# Qwiic_keypad.net
KiCad netlist of a schematic drawn in EAGLE
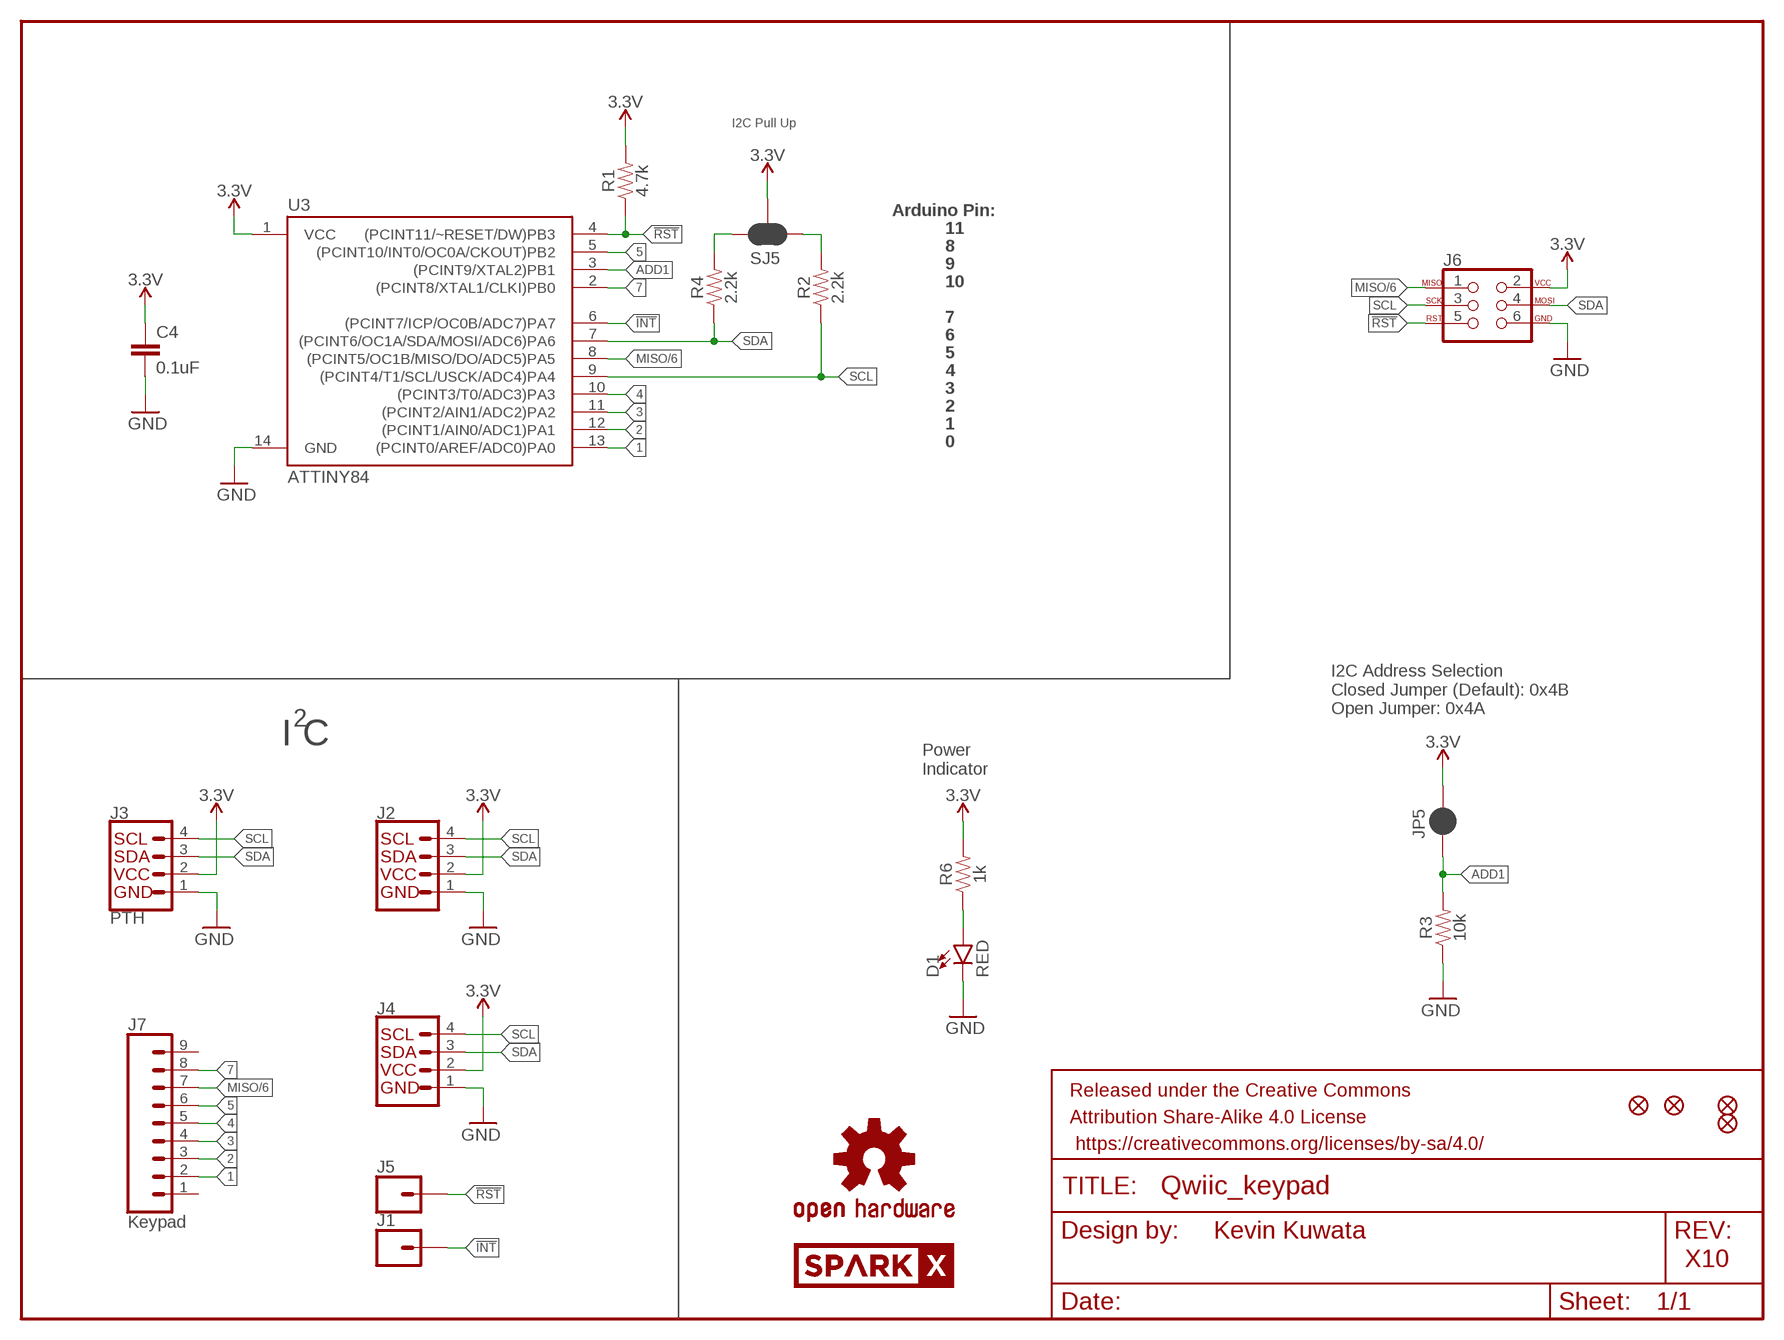
[diagram p0: schematic, sheet 1]

(export (version "E")
  (design (tool "Eeschema 10.0.6"))
  (components
    (comp (ref "C4")
      (value "0.1uF")
      (footprint "eagle-import:0603")
      (libsource (lib "eagle-import") (part "0.1UF-0603-25V-(+80/-20%)"))
    )
    (comp (ref "D1")
      (value "RED")
      (footprint "eagle-import:LED-0603")
      (libsource (lib "eagle-import") (part "LED-RED0603"))
    )
    (comp (ref "FRAME1")
      (value "FRAME-LETTER")
      (footprint "eagle-import:CREATIVE_COMMONS")
      (libsource (lib "eagle-import") (part "FRAME-LETTER"))
    )
    (comp (ref "J1")
      (value "CONN_01PTH_NO_SILK_YES_STOP")
      (footprint "eagle-import:1X01_NO_SILK")
      (libsource (lib "eagle-import") (part "CONN_01PTH_NO_SILK_YES_STOP"))
    )
    (comp (ref "J2")
      (value "QWIIC_CONNECTORJS-1MM")
      (footprint "eagle-import:1X04_1MM_RA")
      (libsource (lib "eagle-import") (part "QWIIC_CONNECTORJS-1MM"))
    )
    (comp (ref "J3")
      (value "PTH")
      (footprint "eagle-import:1X04_NO_SILK")
      (libsource (lib "eagle-import") (part "I2C_STANDARD_NO_SILK"))
    )
    (comp (ref "J4")
      (value "QWIIC_CONNECTORJS-1MM")
      (footprint "eagle-import:1X04_1MM_RA")
      (libsource (lib "eagle-import") (part "QWIIC_CONNECTORJS-1MM"))
    )
    (comp (ref "J5")
      (value "CONN_01PTH_NO_SILK_YES_STOP")
      (footprint "eagle-import:1X01_NO_SILK")
      (libsource (lib "eagle-import") (part "CONN_01PTH_NO_SILK_YES_STOP"))
    )
    (comp (ref "J6")
      (value "AVR_SPI_PROG_3X2TESTPOINTS")
      (footprint "eagle-import:2X3_TEST_POINTS")
      (libsource (lib "eagle-import") (part "AVR_SPI_PROG_3X2TESTPOINTS"))
    )
    (comp (ref "J7")
      (value "Keypad")
      (footprint "eagle-import:1X09_NO_SILK")
      (libsource (lib "eagle-import") (part "CONN_09NO_SILK"))
    )
    (comp (ref "JP1")
      (value "FIDUCIALUFIDUCIAL")
      (footprint "eagle-import:MICRO-FIDUCIAL")
      (libsource (lib "eagle-import") (part "FIDUCIALUFIDUCIAL"))
    )
    (comp (ref "JP2")
      (value "FIDUCIALUFIDUCIAL")
      (footprint "eagle-import:MICRO-FIDUCIAL")
      (libsource (lib "eagle-import") (part "FIDUCIALUFIDUCIAL"))
    )
    (comp (ref "JP3")
      (value "FIDUCIALUFIDUCIAL")
      (footprint "eagle-import:MICRO-FIDUCIAL")
      (libsource (lib "eagle-import") (part "FIDUCIALUFIDUCIAL"))
    )
    (comp (ref "JP5")
      (value "JUMPER-SMT_2_NC_PASTE_NO-SILK")
      (footprint "eagle-import:SMT-JUMPER_2_NC_PASTE_NO-SILK")
      (libsource (lib "eagle-import") (part "JUMPER-SMT_2_NC_PASTE_NO-SILK"))
    )
    (comp (ref "JP6")
      (value "FIDUCIALUFIDUCIAL")
      (footprint "eagle-import:MICRO-FIDUCIAL")
      (libsource (lib "eagle-import") (part "FIDUCIALUFIDUCIAL"))
    )
    (comp (ref "LOGO1")
      (value "OSHW-LOGOMINI")
      (footprint "eagle-import:OSHW-LOGO-MINI")
      (libsource (lib "eagle-import") (part "OSHW-LOGOMINI"))
    )
    (comp (ref "R1")
      (value "4.7k")
      (footprint "eagle-import:0603")
      (libsource (lib "eagle-import") (part "4.7KOHM-0603-1/10W-1%"))
    )
    (comp (ref "R2")
      (value "2.2k")
      (footprint "eagle-import:0603")
      (libsource (lib "eagle-import") (part "2.2KOHM-0603-1/10W-1%"))
    )
    (comp (ref "R3")
      (value "10k")
      (footprint "eagle-import:0603")
      (libsource (lib "eagle-import") (part "10KOHM-0603-1/10W-1%"))
    )
    (comp (ref "R4")
      (value "2.2k")
      (footprint "eagle-import:0603")
      (libsource (lib "eagle-import") (part "2.2KOHM-0603-1/10W-1%"))
    )
    (comp (ref "R6")
      (value "1k")
      (footprint "eagle-import:0603")
      (libsource (lib "eagle-import") (part "1KOHM-0603-1/10W-1%"))
    )
    (comp (ref "SJ5")
      (value "JUMPER-SMT_3_2-NC_PASTE_SILK")
      (footprint "eagle-import:SMT-JUMPER_3_2-NC_PASTE_SILK")
      (libsource (lib "eagle-import") (part "JUMPER-SMT_3_2-NC_PASTE_SILK"))
    )
    (comp (ref "U$1")
      (value "SPARKX-LOGO3")
      (footprint "eagle-import:SPARKX-SMALL")
      (libsource (lib "eagle-import") (part "SPARKX-LOGO3"))
    )
    (comp (ref "U$2")
      (value "SPARKX-LOGO3")
      (footprint "eagle-import:SPARKX-SMALL")
      (libsource (lib "eagle-import") (part "SPARKX-LOGO3"))
    )
    (comp (ref "U3")
      (value "ATTINY84")
      (footprint "eagle-import:SO14")
      (libsource (lib "eagle-import") (part "ATTINY84"))
    )
  )
  (nets
    (net (code "1") (name "/~{INT}") (class "Default")
      (node (ref "J1") (pin "1") (pinfunction "1_1") (pintype "passive"))
      (node (ref "U3") (pin "6") (pinfunction "(PCINT7/ICP/OC0B/ADC7)PA7_6") (pintype "bidirectional"))
    )
    (net (code "2") (name "/~{RST}") (class "Default")
      (node (ref "J5") (pin "1") (pinfunction "1_1") (pintype "passive"))
      (node (ref "J6") (pin "5") (pinfunction "5_5") (pintype "passive"))
      (node (ref "R1") (pin "1") (pinfunction "1_1") (pintype "passive"))
      (node (ref "U3") (pin "4") (pinfunction "(PCINT11/~{RESET/DW})PB3_4") (pintype "bidirectional"))
    )
    (net (code "3") (name "1") (class "Default")
      (node (ref "J7") (pin "2") (pinfunction "2_2") (pintype "passive"))
      (node (ref "U3") (pin "13") (pinfunction "(PCINT0/AREF/ADC0)PA0_13") (pintype "bidirectional"))
    )
    (net (code "4") (name "2") (class "Default")
      (node (ref "J7") (pin "3") (pinfunction "3_3") (pintype "passive"))
      (node (ref "U3") (pin "12") (pinfunction "(PCINT1/AIN0/ADC1)PA1_12") (pintype "bidirectional"))
    )
    (net (code "5") (name "3") (class "Default")
      (node (ref "J7") (pin "4") (pinfunction "4_4") (pintype "passive"))
      (node (ref "U3") (pin "11") (pinfunction "(PCINT2/AIN1/ADC2)PA2_11") (pintype "bidirectional"))
    )
    (net (code "6") (name "3.3V") (class "Default")
      (node (ref "C4") (pin "1") (pinfunction "1_1") (pintype "passive"))
      (node (ref "J2") (pin "2") (pinfunction "2_2") (pintype "power_in"))
      (node (ref "J3") (pin "2") (pinfunction "VCC_2") (pintype "power_in"))
      (node (ref "J4") (pin "2") (pinfunction "2_2") (pintype "power_in"))
      (node (ref "J6") (pin "2") (pinfunction "2_2") (pintype "passive"))
      (node (ref "JP5") (pin "2") (pinfunction "2_2") (pintype "passive"))
      (node (ref "R1") (pin "2") (pinfunction "2_2") (pintype "passive"))
      (node (ref "R6") (pin "2") (pinfunction "2_2") (pintype "passive"))
      (node (ref "SJ5") (pin "2") (pinfunction "2_2") (pintype "passive"))
      (node (ref "U3") (pin "1") (pinfunction "VCC_1") (pintype "bidirectional"))
    )
    (net (code "7") (name "4") (class "Default")
      (node (ref "J7") (pin "5") (pinfunction "5_5") (pintype "passive"))
      (node (ref "U3") (pin "10") (pinfunction "(PCINT3/T0/ADC3)PA3_10") (pintype "bidirectional"))
    )
    (net (code "8") (name "5") (class "Default")
      (node (ref "J7") (pin "6") (pinfunction "6_6") (pintype "passive"))
      (node (ref "U3") (pin "5") (pinfunction "(PCINT10/INT0/OC0A/CKOUT)PB2_5") (pintype "bidirectional"))
    )
    (net (code "9") (name "7") (class "Default")
      (node (ref "J7") (pin "8") (pinfunction "8_8") (pintype "passive"))
      (node (ref "U3") (pin "2") (pinfunction "(PCINT8/XTAL1/CLKI)PB0_2") (pintype "bidirectional"))
    )
    (net (code "10") (name "ADD1") (class "Default")
      (node (ref "JP5") (pin "1") (pinfunction "1_1") (pintype "passive"))
      (node (ref "R3") (pin "2") (pinfunction "2_2") (pintype "passive"))
      (node (ref "U3") (pin "3") (pinfunction "(PCINT9/XTAL2)PB1_3") (pintype "bidirectional"))
    )
    (net (code "11") (name "GND") (class "Default")
      (node (ref "C4") (pin "2") (pinfunction "2_2") (pintype "passive"))
      (node (ref "D1") (pin "C") (pinfunction "C_C") (pintype "passive"))
      (node (ref "J2") (pin "1") (pinfunction "1_1") (pintype "power_in"))
      (node (ref "J3") (pin "1") (pinfunction "GND_1") (pintype "power_in"))
      (node (ref "J4") (pin "1") (pinfunction "1_1") (pintype "power_in"))
      (node (ref "J6") (pin "6") (pinfunction "6_6") (pintype "passive"))
      (node (ref "R3") (pin "1") (pinfunction "1_1") (pintype "passive"))
      (node (ref "U3") (pin "14") (pinfunction "GND_14") (pintype "bidirectional"))
    )
    (net (code "12") (name "MISO{slash}6") (class "Default")
      (node (ref "J6") (pin "1") (pinfunction "1_1") (pintype "passive"))
      (node (ref "J7") (pin "7") (pinfunction "7_7") (pintype "passive"))
      (node (ref "U3") (pin "8") (pinfunction "(PCINT5/OC1B/MISO/DO/ADC5)PA5_8") (pintype "bidirectional"))
    )
    (net (code "13") (name "Net-(D1-PadA)") (class "Default")
      (node (ref "D1") (pin "A") (pinfunction "A_A") (pintype "passive"))
      (node (ref "R6") (pin "1") (pinfunction "1_1") (pintype "passive"))
    )
    (net (code "14") (name "Net-(R2-Pad2)") (class "Default")
      (node (ref "R2") (pin "2") (pinfunction "2_2") (pintype "passive"))
      (node (ref "SJ5") (pin "1") (pinfunction "1_1") (pintype "passive"))
    )
    (net (code "15") (name "Net-(R4-Pad2)") (class "Default")
      (node (ref "R4") (pin "2") (pinfunction "2_2") (pintype "passive"))
      (node (ref "SJ5") (pin "3") (pinfunction "3_3") (pintype "passive"))
    )
    (net (code "16") (name "SCL") (class "Default")
      (node (ref "J2") (pin "4") (pinfunction "4_4") (pintype "passive"))
      (node (ref "J3") (pin "4") (pinfunction "SCL_4") (pintype "passive"))
      (node (ref "J4") (pin "4") (pinfunction "4_4") (pintype "passive"))
      (node (ref "J6") (pin "3") (pinfunction "3_3") (pintype "passive"))
      (node (ref "R2") (pin "1") (pinfunction "1_1") (pintype "passive"))
      (node (ref "U3") (pin "9") (pinfunction "(PCINT4/T1/SCL/USCK/ADC4)PA4_9") (pintype "bidirectional"))
    )
    (net (code "17") (name "SDA") (class "Default")
      (node (ref "J2") (pin "3") (pinfunction "3_3") (pintype "passive"))
      (node (ref "J3") (pin "3") (pinfunction "SDA_3") (pintype "passive"))
      (node (ref "J4") (pin "3") (pinfunction "3_3") (pintype "passive"))
      (node (ref "J6") (pin "4") (pinfunction "4_4") (pintype "passive"))
      (node (ref "R4") (pin "1") (pinfunction "1_1") (pintype "passive"))
      (node (ref "U3") (pin "7") (pinfunction "(PCINT6/OC1A/SDA/MOSI/ADC6)PA6_7") (pintype "bidirectional"))
    )
    (net (code "18") (name "unconnected-(J7-Pad1)") (class "Default")
      (node (ref "J7") (pin "1") (pinfunction "1_1") (pintype "passive"))
    )
    (net (code "19") (name "unconnected-(J7-Pad9)") (class "Default")
      (node (ref "J7") (pin "9") (pinfunction "9_9") (pintype "passive"))
    )
  )
)
